# dimmer_V1.net
KiCad netlist of a schematic drawn in EAGLE
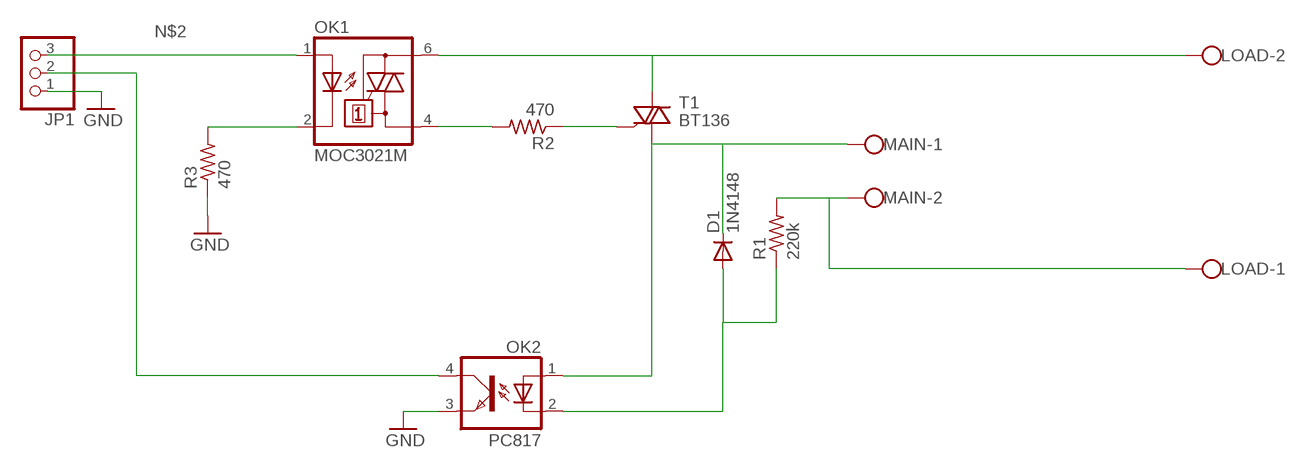
[diagram p0: schematic, sheet 1]

(export (version "E")
  (design (tool "Eeschema 10.0.6"))
  (components
    (comp (ref "D1")
      (value "1N4148")
      (footprint "eagle-import:DO41-10")
      (libsource (lib "eagle-import") (part "1N4004"))
    )
    (comp (ref "JP1")
      (value "PINHD-1X3")
      (footprint "eagle-import:1X03")
      (libsource (lib "eagle-import") (part "PINHD-1X3"))
    )
    (comp (ref "LOAD")
      (value "W237-102")
      (footprint "eagle-import:W237-102")
      (fields (field (name "MPN") "237-102"))
      (libsource (lib "eagle-import") (part "W237-102"))
    )
    (comp (ref "MAIN")
      (value "W237-102")
      (footprint "eagle-import:W237-102")
      (fields (field (name "MPN") "237-102"))
      (libsource (lib "eagle-import") (part "W237-102"))
    )
    (comp (ref "OK1")
      (value "MOC3021M")
      (footprint "eagle-import:DIL06")
      (fields (field (name "MF") "FAIRCHILD SEMICONDUCTOR") (field (name "MPN") "MOC3021-M"))
      (libsource (lib "eagle-import") (part "MOC30M21"))
    )
    (comp (ref "OK2")
      (value "PC817")
      (footprint "eagle-import:DIL04")
      (fields (field (name "MPN") "PC817X4J000F"))
      (libsource (lib "eagle-import") (part "PC817"))
    )
    (comp (ref "R1")
      (value "220k")
      (footprint "eagle-import:0207_10")
      (libsource (lib "eagle-import") (part "R-US_0207/10"))
    )
    (comp (ref "R2")
      (value "470")
      (footprint "eagle-import:0207_10")
      (libsource (lib "eagle-import") (part "R-US_0207/10"))
    )
    (comp (ref "R3")
      (value "470")
      (footprint "eagle-import:0207_10")
      (libsource (lib "eagle-import") (part "R-US_0207/10"))
    )
    (comp (ref "T1")
      (value "BT136")
      (footprint "eagle-import:TO220AB")
      (libsource (lib "eagle-import") (part "BT136"))
    )
  )
  (nets
    (net (code "1") (name "/N$2") (class "Default")
      (node (ref "JP1") (pin "3") (pinfunction "3_3") (pintype "passive"))
      (node (ref "OK1") (pin "1") (pinfunction "A_1") (pintype "passive"))
    )
    (net (code "2") (name "GND") (class "Default")
      (node (ref "JP1") (pin "1") (pinfunction "1_1") (pintype "passive"))
      (node (ref "OK2") (pin "3") (pinfunction "EMIT_3") (pintype "passive"))
      (node (ref "R3") (pin "1") (pinfunction "1_1") (pintype "passive"))
    )
    (net (code "3") (name "Net-(LOADA-KL)") (class "Default")
      (node (ref "LOAD") (pin "1") (pinfunction "KL_1") (pintype "passive"))
      (node (ref "MAIN") (pin "2") (pinfunction "KL_2") (pintype "passive"))
      (node (ref "R1") (pin "2") (pinfunction "2_2") (pintype "passive"))
    )
    (net (code "4") (name "Net-(LOADB-KL)") (class "Default")
      (node (ref "LOAD") (pin "2") (pinfunction "KL_2") (pintype "passive"))
      (node (ref "OK1") (pin "6") (pinfunction "A2_6") (pintype "passive"))
      (node (ref "T1") (pin "2") (pinfunction "A2_2") (pintype "passive"))
    )
    (net (code "5") (name "Net-(MAINA-KL)") (class "Default")
      (node (ref "D1") (pin "C") (pinfunction "C_C") (pintype "passive"))
      (node (ref "MAIN") (pin "1") (pinfunction "KL_1") (pintype "passive"))
      (node (ref "OK2") (pin "1") (pinfunction "A_1") (pintype "passive"))
      (node (ref "T1") (pin "1") (pinfunction "A1_1") (pintype "passive"))
    )
    (net (code "6") (name "Net-(OK1-A1)") (class "Default")
      (node (ref "OK1") (pin "4") (pinfunction "A1_4") (pintype "passive"))
      (node (ref "R2") (pin "2") (pinfunction "2_2") (pintype "passive"))
    )
    (net (code "7") (name "Net-(OK1-C)") (class "Default")
      (node (ref "OK1") (pin "2") (pinfunction "C_2") (pintype "passive"))
      (node (ref "R3") (pin "2") (pinfunction "2_2") (pintype "passive"))
    )
    (net (code "8") (name "Net-(OK2-C)") (class "Default")
      (node (ref "D1") (pin "A") (pinfunction "A_A") (pintype "passive"))
      (node (ref "OK2") (pin "2") (pinfunction "C_2") (pintype "passive"))
      (node (ref "R1") (pin "1") (pinfunction "1_1") (pintype "passive"))
    )
    (net (code "9") (name "Net-(OK2-COL)") (class "Default")
      (node (ref "JP1") (pin "2") (pinfunction "2_2") (pintype "passive"))
      (node (ref "OK2") (pin "4") (pinfunction "COL_4") (pintype "passive"))
    )
    (net (code "10") (name "Net-(T1-G)") (class "Default")
      (node (ref "R2") (pin "1") (pinfunction "1_1") (pintype "passive"))
      (node (ref "T1") (pin "3") (pinfunction "G_3") (pintype "passive"))
    )
  )
)
